# design.net
KiCad netlist of a schematic drawn in Altium Designer
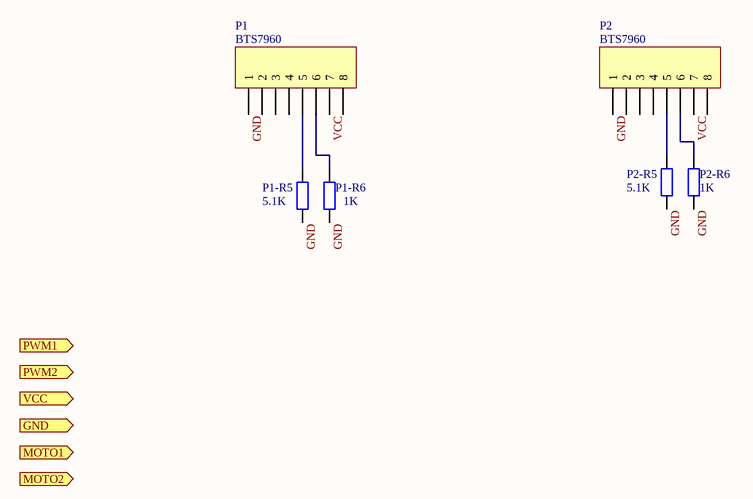
[diagram p0: 电机驱动模块.SchDoc]

(export (version "E")
  (design (tool "Eeschema 10.0.6"))
  (components
    (comp (ref "P1")
      (value "BTS7960")
      (description "Header, 8-Pin")
      (fields (field (name "PUBLISHER") "Altium Limited"))
      (libsource (lib "Miscellaneous Connectors") (part "Header 8"))
    )
    (comp (ref "P1-R5")
      (value "5.1K")
      (footprint "0805")
      (description "Resistor")
      (fields (field (name "PUBLISHER") "Altium Limited"))
      (libsource (lib "Miscellaneous Devices") (part "Res2"))
    )
    (comp (ref "P1-R6")
      (value "1K")
      (footprint "0805")
      (description "Resistor")
      (fields (field (name "PUBLISHER") "Altium Limited"))
      (libsource (lib "Miscellaneous Devices") (part "Res2"))
    )
    (comp (ref "P2")
      (value "BTS7960")
      (description "Header, 8-Pin")
      (fields (field (name "PUBLISHER") "Altium Limited"))
      (libsource (lib "Miscellaneous Connectors") (part "Header 8"))
    )
    (comp (ref "P2-R5")
      (value "5.1K")
      (footprint "0805")
      (description "Resistor")
      (fields (field (name "PUBLISHER") "Altium Limited"))
      (libsource (lib "Miscellaneous Devices") (part "Res2"))
    )
    (comp (ref "P2-R6")
      (value "1K")
      (footprint "0805")
      (description "Resistor")
      (fields (field (name "PUBLISHER") "Altium Limited"))
      (libsource (lib "Miscellaneous Devices") (part "Res2"))
    )
  )
  (nets
    (net (code "1") (name "/GND") (class "Default")
      (node (ref "P1") (pin "1") (pinfunction "1_1") (pintype "passive"))
      (node (ref "P1-R5") (pin "1") (pinfunction "1_1") (pintype "passive"))
      (node (ref "P1-R6") (pin "1") (pinfunction "1_1") (pintype "passive"))
      (node (ref "P2") (pin "1") (pinfunction "1_1") (pintype "passive"))
      (node (ref "P2-R5") (pin "1") (pinfunction "1_1") (pintype "passive"))
      (node (ref "P2-R6") (pin "1") (pinfunction "1_1") (pintype "passive"))
    )
    (net (code "6") (name "/VCC") (class "Default")
      (node (ref "P1") (pin "7") (pinfunction "7_7") (pintype "passive"))
      (node (ref "P2") (pin "7") (pinfunction "7_7") (pintype "passive"))
    )
    (net (code "7") (name "Net-(P1-Pad5)") (class "Default")
      (node (ref "P1") (pin "5") (pinfunction "5_5") (pintype "passive"))
      (node (ref "P1-R5") (pin "2") (pinfunction "2_2") (pintype "passive"))
    )
    (net (code "8") (name "Net-(P1-Pad6)") (class "Default")
      (node (ref "P1") (pin "6") (pinfunction "6_6") (pintype "passive"))
      (node (ref "P1-R6") (pin "2") (pinfunction "2_2") (pintype "passive"))
    )
    (net (code "9") (name "Net-(P2-Pad5)") (class "Default")
      (node (ref "P2") (pin "5") (pinfunction "5_5") (pintype "passive"))
      (node (ref "P2-R5") (pin "2") (pinfunction "2_2") (pintype "passive"))
    )
    (net (code "10") (name "Net-(P2-Pad6)") (class "Default")
      (node (ref "P2") (pin "6") (pinfunction "6_6") (pintype "passive"))
      (node (ref "P2-R6") (pin "2") (pinfunction "2_2") (pintype "passive"))
    )
    (net (code "11") (name "unconnected-(P1-Pad2)") (class "Default")
      (node (ref "P1") (pin "2") (pinfunction "2_2") (pintype "passive"))
    )
    (net (code "12") (name "unconnected-(P1-Pad3)") (class "Default")
      (node (ref "P1") (pin "3") (pinfunction "3_3") (pintype "passive"))
    )
    (net (code "13") (name "unconnected-(P1-Pad4)") (class "Default")
      (node (ref "P1") (pin "4") (pinfunction "4_4") (pintype "passive"))
    )
    (net (code "14") (name "unconnected-(P1-Pad8)") (class "Default")
      (node (ref "P1") (pin "8") (pinfunction "8_8") (pintype "passive"))
    )
    (net (code "15") (name "unconnected-(P2-Pad2)") (class "Default")
      (node (ref "P2") (pin "2") (pinfunction "2_2") (pintype "passive"))
    )
    (net (code "16") (name "unconnected-(P2-Pad3)") (class "Default")
      (node (ref "P2") (pin "3") (pinfunction "3_3") (pintype "passive"))
    )
    (net (code "17") (name "unconnected-(P2-Pad4)") (class "Default")
      (node (ref "P2") (pin "4") (pinfunction "4_4") (pintype "passive"))
    )
    (net (code "18") (name "unconnected-(P2-Pad8)") (class "Default")
      (node (ref "P2") (pin "8") (pinfunction "8_8") (pintype "passive"))
    )
  )
)
